# pcb_02.net
KiCad netlist of a schematic drawn in EAGLE
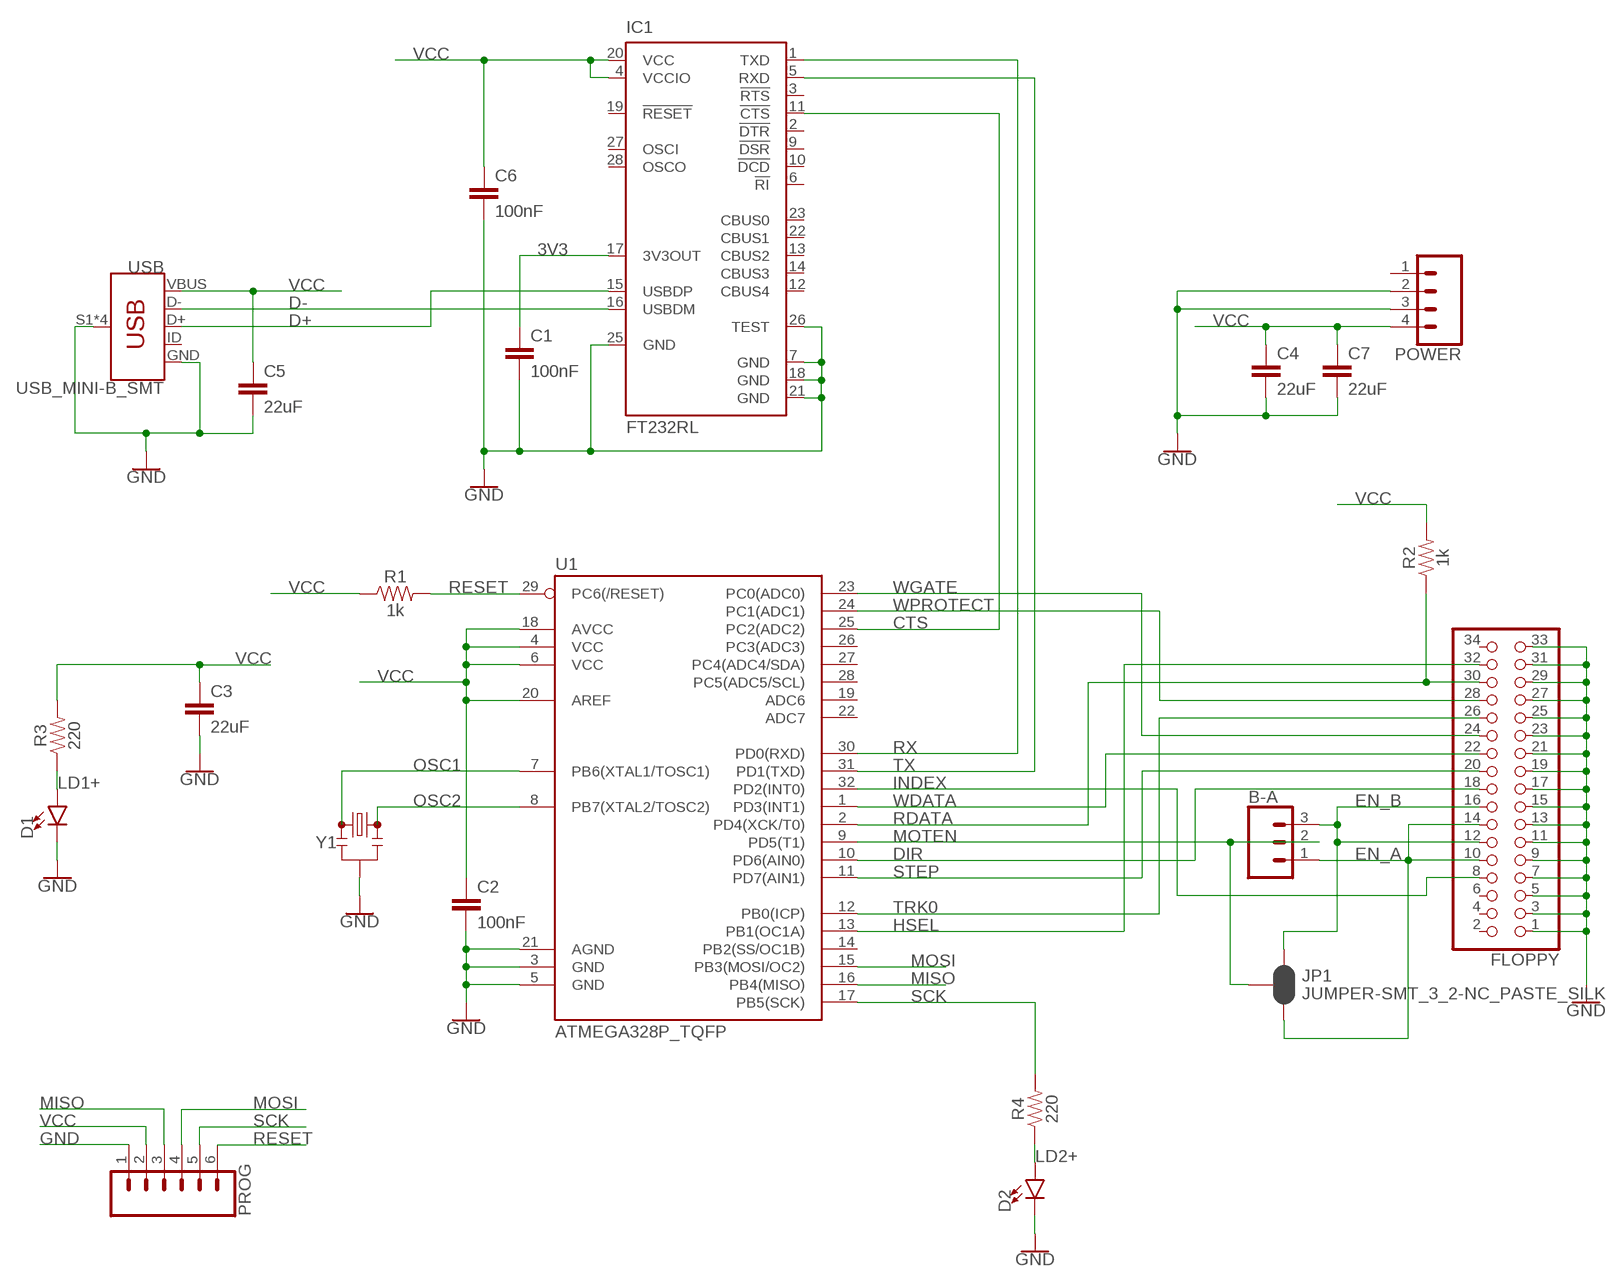
[diagram p0: schematic, sheet 1]

(export (version "E")
  (design (tool "Eeschema 10.0.6"))
  (components
    (comp (ref "B-A")
      (value "CONN_03")
      (footprint "eagle-import:1X03")
      (libsource (lib "eagle-import") (part "CONN_03"))
    )
    (comp (ref "C1")
      (value "100nF")
      (footprint "eagle-import:0603")
      (libsource (lib "eagle-import") (part "1.0UF-0603-16V-10%"))
    )
    (comp (ref "C2")
      (value "100nF")
      (footprint "eagle-import:0603")
      (libsource (lib "eagle-import") (part "1.0UF-0603-16V-10%"))
    )
    (comp (ref "C3")
      (value "22uF")
      (footprint "eagle-import:C0805")
      (libsource (lib "eagle-import") (part "C-EUC0805"))
    )
    (comp (ref "C4")
      (value "22uF")
      (footprint "eagle-import:C0805")
      (libsource (lib "eagle-import") (part "C-EUC0805"))
    )
    (comp (ref "C5")
      (value "22uF")
      (footprint "eagle-import:C0805")
      (libsource (lib "eagle-import") (part "C-EUC0805"))
    )
    (comp (ref "C6")
      (value "100nF")
      (footprint "eagle-import:0603")
      (libsource (lib "eagle-import") (part "1.0UF-0603-16V-10%"))
    )
    (comp (ref "C7")
      (value "22uF")
      (footprint "eagle-import:C0805")
      (libsource (lib "eagle-import") (part "C-EUC0805"))
    )
    (comp (ref "D1")
      (value "LED5MM")
      (footprint "eagle-import:LED_5MM")
      (libsource (lib "eagle-import") (part "LED5MM"))
    )
    (comp (ref "D2")
      (value "LED5MM")
      (footprint "eagle-import:LED_5MM")
      (libsource (lib "eagle-import") (part "LED5MM"))
    )
    (comp (ref "FLOPPY")
      (value "PINHD-2X17_2.54-90°")
      (footprint "eagle-import:2X17_90")
      (libsource (lib "eagle-import") (part "PINHD-2X17_2.54-90°"))
    )
    (comp (ref "IC1")
      (value "FT232RL")
      (footprint "eagle-import:SSOP28")
      (libsource (lib "eagle-import") (part "FT232RL"))
    )
    (comp (ref "JP1")
      (value "JUMPER-SMT_3_2-NC_PASTE_SILK")
      (footprint "eagle-import:SMT-JUMPER_3_2-NC_PASTE_SILK")
      (libsource (lib "eagle-import") (part "JUMPER-SMT_3_2-NC_PASTE_SILK"))
    )
    (comp (ref "POWER")
      (value "CONN_04")
      (footprint "eagle-import:1X04")
      (libsource (lib "eagle-import") (part "CONN_04"))
    )
    (comp (ref "PROG")
      (value "CONN_06SILK_FEMALE_PTH")
      (footprint "eagle-import:1X06")
      (libsource (lib "eagle-import") (part "CONN_06SILK_FEMALE_PTH"))
    )
    (comp (ref "R1")
      (value "1k")
      (footprint "eagle-import:0603")
      (libsource (lib "eagle-import") (part "10KOHM-0603-1/10W-1%"))
    )
    (comp (ref "R2")
      (value "1k")
      (footprint "eagle-import:0603")
      (libsource (lib "eagle-import") (part "10KOHM-0603-1/10W-1%"))
    )
    (comp (ref "R3")
      (value "220")
      (footprint "eagle-import:0603")
      (libsource (lib "eagle-import") (part "10KOHM-0603-1/10W-1%"))
    )
    (comp (ref "R4")
      (value "220")
      (footprint "eagle-import:0603")
      (libsource (lib "eagle-import") (part "10KOHM-0603-1/10W-1%"))
    )
    (comp (ref "U1")
      (value "ATMEGA328P_TQFP")
      (footprint "eagle-import:TQFP32-08")
      (libsource (lib "eagle-import") (part "ATMEGA328P_TQFP"))
    )
    (comp (ref "USB")
      (value "USB_MINI-B_SMT")
      (footprint "eagle-import:USB-MINIB")
      (libsource (lib "eagle-import") (part "USB_MINI-B_SMT"))
    )
    (comp (ref "Y1")
      (value "RESONATORSMD-3.2X1.3")
      (footprint "eagle-import:RESONATOR-SMD-3.2X1.3")
      (libsource (lib "eagle-import") (part "RESONATORSMD-3.2X1.3"))
    )
  )
  (nets
    (net (code "1") (name "/3V3") (class "Default")
      (node (ref "C1") (pin "1") (pinfunction "1_1") (pintype "passive"))
      (node (ref "IC1") (pin "17") (pinfunction "3V3OUT_17") (pintype "output"))
    )
    (net (code "2") (name "/CTS") (class "Default")
      (node (ref "IC1") (pin "11") (pinfunction "~{CTS}_11") (pintype "input"))
      (node (ref "U1") (pin "25") (pinfunction "PC2(ADC2)_25") (pintype "bidirectional"))
    )
    (net (code "3") (name "/D+") (class "Default")
      (node (ref "IC1") (pin "15") (pinfunction "USBDP_15") (pintype "bidirectional"))
      (node (ref "USB") (pin "D+") (pinfunction "D+_D+") (pintype "bidirectional"))
    )
    (net (code "4") (name "/D-") (class "Default")
      (node (ref "IC1") (pin "16") (pinfunction "USBDM_16") (pintype "bidirectional"))
      (node (ref "USB") (pin "D-") (pinfunction "D-_D-") (pintype "bidirectional"))
    )
    (net (code "5") (name "/DIR") (class "Default")
      (node (ref "FLOPPY") (pin "18") (pinfunction "18_18") (pintype "passive"))
      (node (ref "U1") (pin "10") (pinfunction "PD6(AIN0)_10") (pintype "bidirectional"))
    )
    (net (code "6") (name "/EN_A") (class "Default")
      (node (ref "B-A") (pin "1") (pinfunction "1_1") (pintype "passive"))
      (node (ref "FLOPPY") (pin "10") (pinfunction "10_10") (pintype "passive"))
      (node (ref "FLOPPY") (pin "14") (pinfunction "14_14") (pintype "passive"))
      (node (ref "JP1") (pin "3") (pinfunction "3_3") (pintype "passive"))
    )
    (net (code "7") (name "/EN_B") (class "Default")
      (node (ref "B-A") (pin "3") (pinfunction "3_3") (pintype "passive"))
      (node (ref "FLOPPY") (pin "12") (pinfunction "12_12") (pintype "passive"))
      (node (ref "FLOPPY") (pin "16") (pinfunction "16_16") (pintype "passive"))
      (node (ref "JP1") (pin "1") (pinfunction "1_1") (pintype "passive"))
    )
    (net (code "8") (name "/HSEL") (class "Default")
      (node (ref "FLOPPY") (pin "32") (pinfunction "32_32") (pintype "passive"))
      (node (ref "U1") (pin "13") (pinfunction "PB1(OC1A)_13") (pintype "bidirectional"))
    )
    (net (code "9") (name "/INDEX") (class "Default")
      (node (ref "FLOPPY") (pin "8") (pinfunction "8_8") (pintype "passive"))
      (node (ref "U1") (pin "32") (pinfunction "PD2(INT0)_32") (pintype "bidirectional"))
    )
    (net (code "10") (name "/LD1+") (class "Default")
      (node (ref "D1") (pin "A") (pinfunction "A_A") (pintype "passive"))
      (node (ref "R3") (pin "1") (pinfunction "1_1") (pintype "passive"))
    )
    (net (code "11") (name "/LD2+") (class "Default")
      (node (ref "D2") (pin "A") (pinfunction "A_A") (pintype "passive"))
      (node (ref "R4") (pin "1") (pinfunction "1_1") (pintype "passive"))
    )
    (net (code "12") (name "/MISO") (class "Default")
      (node (ref "PROG") (pin "3") (pinfunction "3_3") (pintype "passive"))
      (node (ref "U1") (pin "16") (pinfunction "PB4(MISO)_16") (pintype "bidirectional"))
    )
    (net (code "13") (name "/MOSI") (class "Default")
      (node (ref "PROG") (pin "4") (pinfunction "4_4") (pintype "passive"))
      (node (ref "U1") (pin "15") (pinfunction "PB3(MOSI/OC2)_15") (pintype "bidirectional"))
    )
    (net (code "14") (name "/MOTEN") (class "Default")
      (node (ref "B-A") (pin "2") (pinfunction "2_2") (pintype "passive"))
      (node (ref "JP1") (pin "2") (pinfunction "2_2") (pintype "passive"))
      (node (ref "U1") (pin "9") (pinfunction "PD5(T1)_9") (pintype "bidirectional"))
    )
    (net (code "15") (name "/OSC1") (class "Default")
      (node (ref "U1") (pin "7") (pinfunction "PB6(XTAL1/TOSC1)_7") (pintype "bidirectional"))
      (node (ref "Y1") (pin "1") (pinfunction "1_1") (pintype "passive"))
    )
    (net (code "16") (name "/OSC2") (class "Default")
      (node (ref "U1") (pin "8") (pinfunction "PB7(XTAL2/TOSC2)_8") (pintype "bidirectional"))
      (node (ref "Y1") (pin "3") (pinfunction "3_3") (pintype "passive"))
    )
    (net (code "17") (name "/RDATA") (class "Default")
      (node (ref "FLOPPY") (pin "30") (pinfunction "30_30") (pintype "passive"))
      (node (ref "R2") (pin "1") (pinfunction "1_1") (pintype "passive"))
      (node (ref "U1") (pin "2") (pinfunction "PD4(XCK/T0)_2") (pintype "bidirectional"))
    )
    (net (code "18") (name "/RESET") (class "Default")
      (node (ref "PROG") (pin "6") (pinfunction "6_6") (pintype "passive"))
      (node (ref "R1") (pin "2") (pinfunction "2_2") (pintype "passive"))
      (node (ref "U1") (pin "29") (pinfunction "PC6(/RESET)_29") (pintype "bidirectional"))
    )
    (net (code "19") (name "/RX") (class "Default")
      (node (ref "IC1") (pin "1") (pinfunction "TXD_1") (pintype "output"))
      (node (ref "U1") (pin "30") (pinfunction "PD0(RXD)_30") (pintype "bidirectional"))
    )
    (net (code "20") (name "/SCK") (class "Default")
      (node (ref "PROG") (pin "5") (pinfunction "5_5") (pintype "passive"))
      (node (ref "R4") (pin "2") (pinfunction "2_2") (pintype "passive"))
      (node (ref "U1") (pin "17") (pinfunction "PB5(SCK)_17") (pintype "bidirectional"))
    )
    (net (code "21") (name "/STEP") (class "Default")
      (node (ref "FLOPPY") (pin "20") (pinfunction "20_20") (pintype "passive"))
      (node (ref "U1") (pin "11") (pinfunction "PD7(AIN1)_11") (pintype "bidirectional"))
    )
    (net (code "22") (name "/TRK0") (class "Default")
      (node (ref "FLOPPY") (pin "26") (pinfunction "26_26") (pintype "passive"))
      (node (ref "U1") (pin "12") (pinfunction "PB0(ICP)_12") (pintype "bidirectional"))
    )
    (net (code "23") (name "/TX") (class "Default")
      (node (ref "IC1") (pin "5") (pinfunction "RXD_5") (pintype "input"))
      (node (ref "U1") (pin "31") (pinfunction "PD1(TXD)_31") (pintype "bidirectional"))
    )
    (net (code "24") (name "/VCC") (class "Default")
      (node (ref "C2") (pin "1") (pinfunction "1_1") (pintype "passive"))
      (node (ref "C3") (pin "1") (pinfunction "1_1") (pintype "passive"))
      (node (ref "C4") (pin "1") (pinfunction "1_1") (pintype "passive"))
      (node (ref "C5") (pin "1") (pinfunction "1_1") (pintype "passive"))
      (node (ref "C6") (pin "1") (pinfunction "1_1") (pintype "passive"))
      (node (ref "C7") (pin "1") (pinfunction "1_1") (pintype "passive"))
      (node (ref "IC1") (pin "20") (pinfunction "VCC_20") (pintype "power_in"))
      (node (ref "IC1") (pin "4") (pinfunction "VCCIO_4") (pintype "power_in"))
      (node (ref "POWER") (pin "4") (pinfunction "4_4") (pintype "passive"))
      (node (ref "PROG") (pin "2") (pinfunction "2_2") (pintype "passive"))
      (node (ref "R1") (pin "1") (pinfunction "1_1") (pintype "passive"))
      (node (ref "R2") (pin "2") (pinfunction "2_2") (pintype "passive"))
      (node (ref "R3") (pin "2") (pinfunction "2_2") (pintype "passive"))
      (node (ref "U1") (pin "18") (pinfunction "AVCC_18") (pintype "bidirectional"))
      (node (ref "U1") (pin "20") (pinfunction "AREF_20") (pintype "bidirectional"))
      (node (ref "U1") (pin "4") (pinfunction "VCC_4") (pintype "bidirectional"))
      (node (ref "U1") (pin "6") (pinfunction "VCC_6") (pintype "bidirectional"))
      (node (ref "USB") (pin "VBUS") (pinfunction "VBUS_VBUS") (pintype "power_in"))
    )
    (net (code "25") (name "/WDATA") (class "Default")
      (node (ref "FLOPPY") (pin "22") (pinfunction "22_22") (pintype "passive"))
      (node (ref "U1") (pin "1") (pinfunction "PD3(INT1)_1") (pintype "bidirectional"))
    )
    (net (code "26") (name "/WGATE") (class "Default")
      (node (ref "FLOPPY") (pin "24") (pinfunction "24_24") (pintype "passive"))
      (node (ref "U1") (pin "23") (pinfunction "PC0(ADC0)_23") (pintype "bidirectional"))
    )
    (net (code "27") (name "/WPROTECT") (class "Default")
      (node (ref "FLOPPY") (pin "28") (pinfunction "28_28") (pintype "passive"))
      (node (ref "U1") (pin "24") (pinfunction "PC1(ADC1)_24") (pintype "bidirectional"))
    )
    (net (code "28") (name "GND") (class "Default")
      (node (ref "C1") (pin "2") (pinfunction "2_2") (pintype "passive"))
      (node (ref "C2") (pin "2") (pinfunction "2_2") (pintype "passive"))
      (node (ref "C3") (pin "2") (pinfunction "2_2") (pintype "passive"))
      (node (ref "C4") (pin "2") (pinfunction "2_2") (pintype "passive"))
      (node (ref "C5") (pin "2") (pinfunction "2_2") (pintype "passive"))
      (node (ref "C6") (pin "2") (pinfunction "2_2") (pintype "passive"))
      (node (ref "C7") (pin "2") (pinfunction "2_2") (pintype "passive"))
      (node (ref "D1") (pin "K") (pinfunction "C_K") (pintype "passive"))
      (node (ref "D2") (pin "K") (pinfunction "C_K") (pintype "passive"))
      (node (ref "FLOPPY") (pin "1") (pinfunction "1_1") (pintype "passive"))
      (node (ref "FLOPPY") (pin "11") (pinfunction "11_11") (pintype "passive"))
      (node (ref "FLOPPY") (pin "13") (pinfunction "13_13") (pintype "passive"))
      (node (ref "FLOPPY") (pin "15") (pinfunction "15_15") (pintype "passive"))
      (node (ref "FLOPPY") (pin "17") (pinfunction "17_17") (pintype "passive"))
      (node (ref "FLOPPY") (pin "19") (pinfunction "19_19") (pintype "passive"))
      (node (ref "FLOPPY") (pin "21") (pinfunction "21_21") (pintype "passive"))
      (node (ref "FLOPPY") (pin "23") (pinfunction "23_23") (pintype "passive"))
      (node (ref "FLOPPY") (pin "25") (pinfunction "25_25") (pintype "passive"))
      (node (ref "FLOPPY") (pin "27") (pinfunction "27_27") (pintype "passive"))
      (node (ref "FLOPPY") (pin "29") (pinfunction "29_29") (pintype "passive"))
      (node (ref "FLOPPY") (pin "3") (pinfunction "3_3") (pintype "passive"))
      (node (ref "FLOPPY") (pin "31") (pinfunction "31_31") (pintype "passive"))
      (node (ref "FLOPPY") (pin "33") (pinfunction "33_33") (pintype "passive"))
      (node (ref "FLOPPY") (pin "5") (pinfunction "5_5") (pintype "passive"))
      (node (ref "FLOPPY") (pin "7") (pinfunction "7_7") (pintype "passive"))
      (node (ref "FLOPPY") (pin "9") (pinfunction "9_9") (pintype "passive"))
      (node (ref "IC1") (pin "18") (pinfunction "GND_18") (pintype "power_in"))
      (node (ref "IC1") (pin "21") (pinfunction "GND_21") (pintype "power_in"))
      (node (ref "IC1") (pin "25") (pinfunction "GND_25") (pintype "power_in"))
      (node (ref "IC1") (pin "26") (pinfunction "TEST_26") (pintype "input"))
      (node (ref "IC1") (pin "7") (pinfunction "GND_7") (pintype "power_in"))
      (node (ref "POWER") (pin "2") (pinfunction "2_2") (pintype "passive"))
      (node (ref "POWER") (pin "3") (pinfunction "3_3") (pintype "passive"))
      (node (ref "PROG") (pin "1") (pinfunction "1_1") (pintype "passive"))
      (node (ref "U1") (pin "21") (pinfunction "AGND_21") (pintype "bidirectional"))
      (node (ref "U1") (pin "3") (pinfunction "GND_3") (pintype "bidirectional"))
      (node (ref "U1") (pin "5") (pinfunction "GND_5") (pintype "bidirectional"))
      (node (ref "USB") (pin "GND") (pinfunction "GND_GND") (pintype "power_in"))
      (node (ref "USB") (pin "S1") (pinfunction "SHIELD_S1") (pintype "bidirectional"))
      (node (ref "USB") (pin "S2") (pinfunction "SHIELD_S2") (pintype "bidirectional"))
      (node (ref "USB") (pin "S3") (pinfunction "SHIELD_S3") (pintype "bidirectional"))
      (node (ref "USB") (pin "S4") (pinfunction "SHIELD_S4") (pintype "bidirectional"))
      (node (ref "Y1") (pin "2") (pinfunction "2_2") (pintype "passive"))
    )
    (net (code "29") (name "unconnected-(FLOPPY-Pad2)") (class "Default")
      (node (ref "FLOPPY") (pin "2") (pinfunction "2_2") (pintype "passive"))
    )
    (net (code "30") (name "unconnected-(FLOPPY-Pad4)") (class "Default")
      (node (ref "FLOPPY") (pin "4") (pinfunction "4_4") (pintype "passive"))
    )
    (net (code "31") (name "unconnected-(FLOPPY-Pad6)") (class "Default")
      (node (ref "FLOPPY") (pin "6") (pinfunction "6_6") (pintype "passive"))
    )
    (net (code "32") (name "unconnected-(FLOPPY-Pad34)") (class "Default")
      (node (ref "FLOPPY") (pin "34") (pinfunction "34_34") (pintype "passive"))
    )
    (net (code "33") (name "unconnected-(IC1-CBUS0-Pad23)") (class "Default")
      (node (ref "IC1") (pin "23") (pinfunction "CBUS0_23") (pintype "bidirectional"))
    )
    (net (code "34") (name "unconnected-(IC1-CBUS1-Pad22)") (class "Default")
      (node (ref "IC1") (pin "22") (pinfunction "CBUS1_22") (pintype "bidirectional"))
    )
    (net (code "35") (name "unconnected-(IC1-CBUS2-Pad13)") (class "Default")
      (node (ref "IC1") (pin "13") (pinfunction "CBUS2_13") (pintype "bidirectional"))
    )
    (net (code "36") (name "unconnected-(IC1-CBUS3-Pad14)") (class "Default")
      (node (ref "IC1") (pin "14") (pinfunction "CBUS3_14") (pintype "bidirectional"))
    )
    (net (code "37") (name "unconnected-(IC1-CBUS4-Pad12)") (class "Default")
      (node (ref "IC1") (pin "12") (pinfunction "CBUS4_12") (pintype "bidirectional"))
    )
    (net (code "38") (name "unconnected-(IC1-OSCI-Pad27)") (class "Default")
      (node (ref "IC1") (pin "27") (pinfunction "OSCI_27") (pintype "input"))
    )
    (net (code "39") (name "unconnected-(IC1-OSCO-Pad28)") (class "Default")
      (node (ref "IC1") (pin "28") (pinfunction "OSCO_28") (pintype "output"))
    )
    (net (code "40") (name "unconnected-(IC1-~{DCD}-Pad10)") (class "Default")
      (node (ref "IC1") (pin "10") (pinfunction "~{DCD}_10") (pintype "input"))
    )
    (net (code "41") (name "unconnected-(IC1-~{DSR}-Pad9)") (class "Default")
      (node (ref "IC1") (pin "9") (pinfunction "~{DSR}_9") (pintype "input"))
    )
    (net (code "42") (name "unconnected-(IC1-~{DTR}-Pad2)") (class "Default")
      (node (ref "IC1") (pin "2") (pinfunction "~{DTR}_2") (pintype "output"))
    )
    (net (code "43") (name "unconnected-(IC1-~{RESET}-Pad19)") (class "Default")
      (node (ref "IC1") (pin "19") (pinfunction "~{RESET}_19") (pintype "input"))
    )
    (net (code "44") (name "unconnected-(IC1-~{RI}-Pad6)") (class "Default")
      (node (ref "IC1") (pin "6") (pinfunction "~{RI}_6") (pintype "input"))
    )
    (net (code "45") (name "unconnected-(IC1-~{RTS}-Pad3)") (class "Default")
      (node (ref "IC1") (pin "3") (pinfunction "~{RTS}_3") (pintype "output"))
    )
    (net (code "46") (name "unconnected-(POWER-Pad1)") (class "Default")
      (node (ref "POWER") (pin "1") (pinfunction "1_1") (pintype "passive"))
    )
    (net (code "47") (name "unconnected-(U1-ADC6-Pad19)") (class "Default")
      (node (ref "U1") (pin "19") (pinfunction "ADC6_19") (pintype "bidirectional"))
    )
    (net (code "48") (name "unconnected-(U1-ADC7-Pad22)") (class "Default")
      (node (ref "U1") (pin "22") (pinfunction "ADC7_22") (pintype "bidirectional"))
    )
    (net (code "49") (name "unconnected-(U1-PB2(SS{slash}OC1B)-Pad14)") (class "Default")
      (node (ref "U1") (pin "14") (pinfunction "PB2(SS/OC1B)_14") (pintype "bidirectional"))
    )
    (net (code "50") (name "unconnected-(U1-PC3(ADC3)-Pad26)") (class "Default")
      (node (ref "U1") (pin "26") (pinfunction "PC3(ADC3)_26") (pintype "bidirectional"))
    )
    (net (code "51") (name "unconnected-(U1-PC4(ADC4{slash}SDA)-Pad27)") (class "Default")
      (node (ref "U1") (pin "27") (pinfunction "PC4(ADC4/SDA)_27") (pintype "bidirectional"))
    )
    (net (code "52") (name "unconnected-(U1-PC5(ADC5{slash}SCL)-Pad28)") (class "Default")
      (node (ref "U1") (pin "28") (pinfunction "PC5(ADC5/SCL)_28") (pintype "bidirectional"))
    )
    (net (code "53") (name "unconnected-(USB-PadID)") (class "Default")
      (node (ref "USB") (pin "ID") (pinfunction "ID_ID") (pintype "bidirectional"))
    )
  )
)
